# switchmod.net
KiCad netlist of a schematic drawn in EAGLE
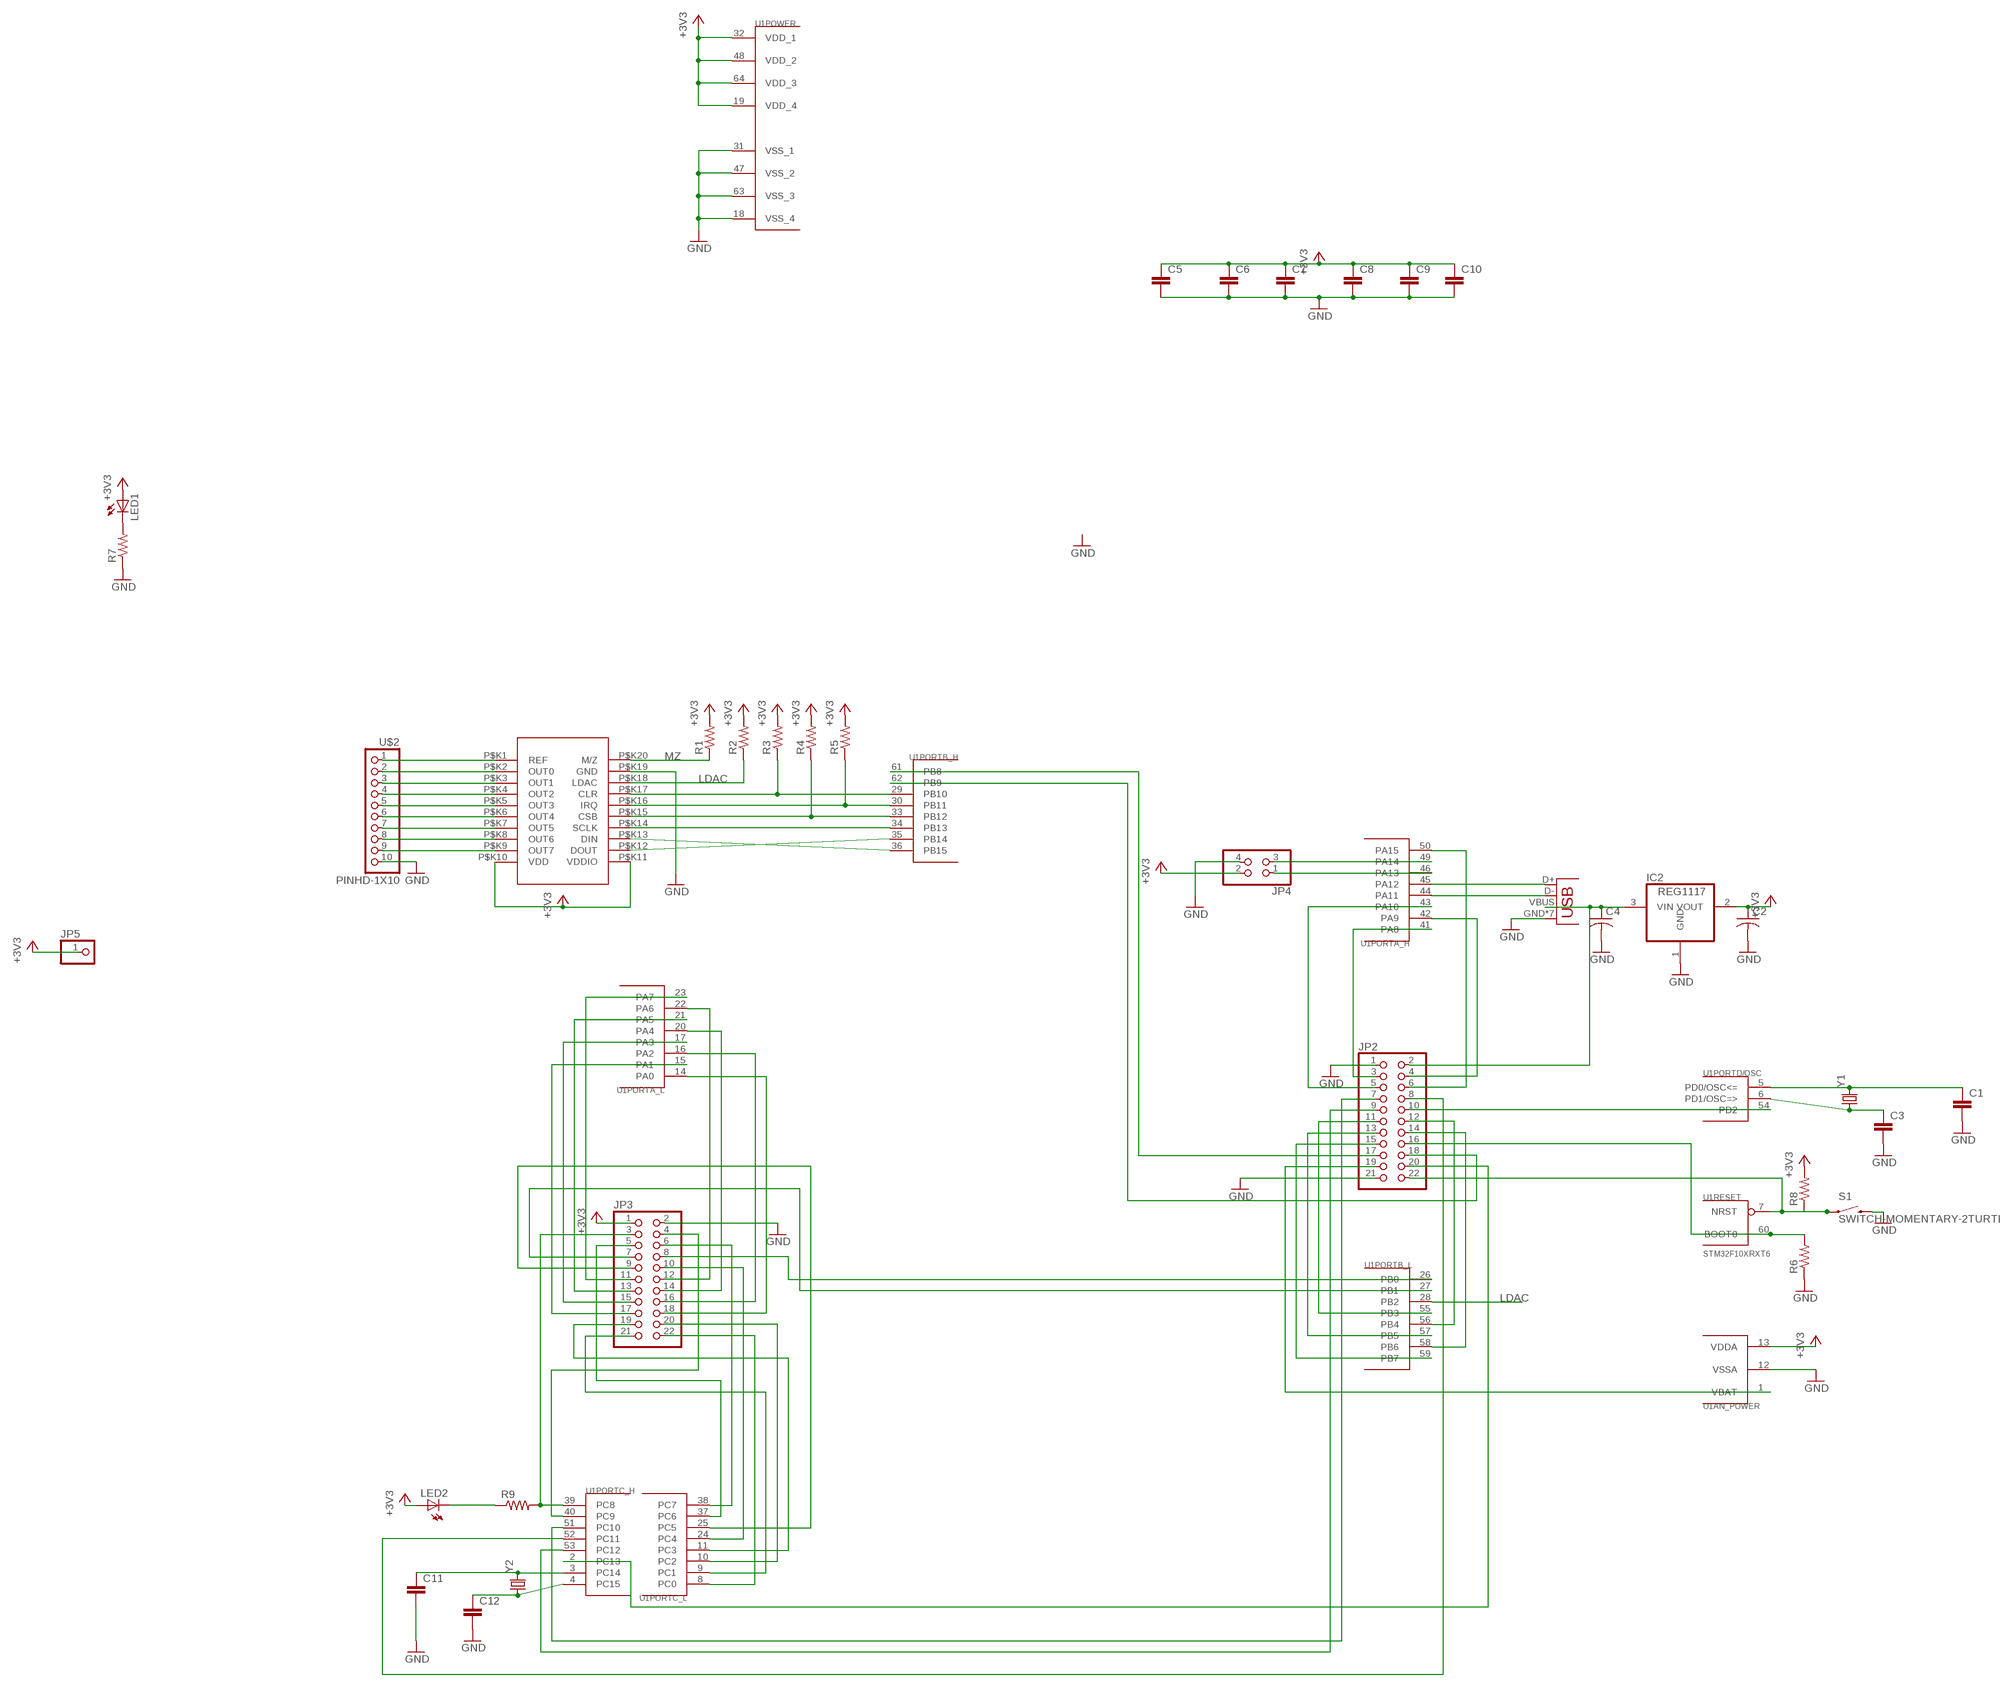
[diagram p0: schematic, sheet 1]

(export (version "E")
  (design (tool "Eeschema 10.0.6"))
  (components
    (comp (ref "C1")
      (value "CAP0805")
      (footprint "eagle-import:0805")
      (libsource (lib "eagle-import") (part "CAP0805"))
    )
    (comp (ref "C2")
      (value "C-USC1210")
      (footprint "eagle-import:C1210")
      (libsource (lib "eagle-import") (part "C-USC1210"))
    )
    (comp (ref "C3")
      (value "CAP0805")
      (footprint "eagle-import:0805")
      (libsource (lib "eagle-import") (part "CAP0805"))
    )
    (comp (ref "C4")
      (value "C-USC1210")
      (footprint "eagle-import:C1210")
      (libsource (lib "eagle-import") (part "C-USC1210"))
    )
    (comp (ref "C5")
      (value "CAP0805")
      (footprint "eagle-import:0805")
      (libsource (lib "eagle-import") (part "CAP0805"))
    )
    (comp (ref "C6")
      (value "CAP0805")
      (footprint "eagle-import:0805")
      (libsource (lib "eagle-import") (part "CAP0805"))
    )
    (comp (ref "C7")
      (value "CAP0805")
      (footprint "eagle-import:0805")
      (libsource (lib "eagle-import") (part "CAP0805"))
    )
    (comp (ref "C8")
      (value "CAP0805")
      (footprint "eagle-import:0805")
      (libsource (lib "eagle-import") (part "CAP0805"))
    )
    (comp (ref "C9")
      (value "CAP0805")
      (footprint "eagle-import:0805")
      (libsource (lib "eagle-import") (part "CAP0805"))
    )
    (comp (ref "C10")
      (value "CAP0805")
      (footprint "eagle-import:0805")
      (libsource (lib "eagle-import") (part "CAP0805"))
    )
    (comp (ref "C11")
      (value "CAP0805")
      (footprint "eagle-import:0805")
      (libsource (lib "eagle-import") (part "CAP0805"))
    )
    (comp (ref "C12")
      (value "CAP0805")
      (footprint "eagle-import:0805")
      (libsource (lib "eagle-import") (part "CAP0805"))
    )
    (comp (ref "IC2")
      (value "REG1117")
      (footprint "eagle-import:SOT223")
      (libsource (lib "eagle-import") (part "REG1117"))
    )
    (comp (ref "JP2")
      (value "PINHD-2X11")
      (footprint "eagle-import:2X11")
      (libsource (lib "eagle-import") (part "PINHD-2X11"))
    )
    (comp (ref "JP3")
      (value "PINHD-2X11")
      (footprint "eagle-import:2X11")
      (libsource (lib "eagle-import") (part "PINHD-2X11"))
    )
    (comp (ref "JP4")
      (value "PINHD-2X2")
      (footprint "eagle-import:2X02")
      (libsource (lib "eagle-import") (part "PINHD-2X2"))
    )
    (comp (ref "JP5")
      (value "PINHD-1X1")
      (footprint "eagle-import:1X01")
      (libsource (lib "eagle-import") (part "PINHD-1X1"))
    )
    (comp (ref "LED1")
      (value "LEDCHIP-LED0805")
      (footprint "eagle-import:CHIP-LED0805")
      (libsource (lib "eagle-import") (part "LEDCHIP-LED0805"))
    )
    (comp (ref "LED2")
      (value "LEDCHIP-LED0805")
      (footprint "eagle-import:CHIP-LED0805")
      (libsource (lib "eagle-import") (part "LEDCHIP-LED0805"))
    )
    (comp (ref "R1")
      (value "RESISTOR0805-RES")
      (footprint "eagle-import:0805")
      (libsource (lib "eagle-import") (part "RESISTOR0805-RES"))
    )
    (comp (ref "R2")
      (value "RESISTOR0805-RES")
      (footprint "eagle-import:0805")
      (libsource (lib "eagle-import") (part "RESISTOR0805-RES"))
    )
    (comp (ref "R3")
      (value "RESISTOR0805-RES")
      (footprint "eagle-import:0805")
      (libsource (lib "eagle-import") (part "RESISTOR0805-RES"))
    )
    (comp (ref "R4")
      (value "RESISTOR0805-RES")
      (footprint "eagle-import:0805")
      (libsource (lib "eagle-import") (part "RESISTOR0805-RES"))
    )
    (comp (ref "R5")
      (value "RESISTOR0805-RES")
      (footprint "eagle-import:0805")
      (libsource (lib "eagle-import") (part "RESISTOR0805-RES"))
    )
    (comp (ref "R6")
      (value "RESISTOR0805-RES")
      (footprint "eagle-import:0805")
      (libsource (lib "eagle-import") (part "RESISTOR0805-RES"))
    )
    (comp (ref "R7")
      (value "RESISTOR0805-RES")
      (footprint "eagle-import:0805")
      (libsource (lib "eagle-import") (part "RESISTOR0805-RES"))
    )
    (comp (ref "R8")
      (value "RESISTOR0805-RES")
      (footprint "eagle-import:0805")
      (libsource (lib "eagle-import") (part "RESISTOR0805-RES"))
    )
    (comp (ref "R9")
      (value "RESISTOR0805-RES")
      (footprint "eagle-import:0805")
      (libsource (lib "eagle-import") (part "RESISTOR0805-RES"))
    )
    (comp (ref "S1")
      (value "SWITCH-MOMENTARY-2TURTLE")
      (footprint "eagle-import:KMR2")
      (libsource (lib "eagle-import") (part "SWITCH-MOMENTARY-2TURTLE"))
    )
    (comp (ref "U$1")
      (value "MAX572X")
      (footprint "eagle-import:TSSOP20")
      (libsource (lib "eagle-import") (part "MAX572X"))
    )
    (comp (ref "U$2")
      (value "PINHD-1X10")
      (footprint "eagle-import:1X10-BIG")
      (libsource (lib "eagle-import") (part "PINHD-1X10"))
    )
    (comp (ref "U1")
      (value "STM32F10XRXT6")
      (footprint "eagle-import:TQFP64")
      (libsource (lib "eagle-import") (part "STM32F10XRXT6"))
    )
    (comp (ref "X1")
      (value "USB-MICROB")
      (footprint "eagle-import:USB-MICROB")
      (libsource (lib "eagle-import") (part "USB-MICROB"))
    )
    (comp (ref "Y1")
      (value "CRYSTALHC49US")
      (footprint "eagle-import:HC49US")
      (libsource (lib "eagle-import") (part "CRYSTALHC49US"))
    )
    (comp (ref "Y2")
      (value "CRYSTALTC26H_EZ")
      (footprint "eagle-import:TC26HEZ")
      (libsource (lib "eagle-import") (part "CRYSTALTC26H_EZ"))
    )
  )
  (nets
    (net (code "1") (name "+3V3") (class "Default")
      (node (ref "C10") (pin "1") (pinfunction "1_1") (pintype "passive"))
      (node (ref "C2") (pin "1") (pinfunction "1_1") (pintype "passive"))
      (node (ref "C5") (pin "1") (pinfunction "1_1") (pintype "passive"))
      (node (ref "C6") (pin "1") (pinfunction "1_1") (pintype "passive"))
      (node (ref "C7") (pin "1") (pinfunction "1_1") (pintype "passive"))
      (node (ref "C8") (pin "1") (pinfunction "1_1") (pintype "passive"))
      (node (ref "C9") (pin "1") (pinfunction "1_1") (pintype "passive"))
      (node (ref "IC2") (pin "2") (pinfunction "VOUT_2") (pintype "output"))
      (node (ref "JP3") (pin "1") (pinfunction "1_1") (pintype "passive"))
      (node (ref "JP4") (pin "2") (pinfunction "2_2") (pintype "passive"))
      (node (ref "JP5") (pin "1") (pinfunction "1_1") (pintype "passive"))
      (node (ref "LED1") (pin "A") (pinfunction "A_A") (pintype "passive"))
      (node (ref "LED2") (pin "A") (pinfunction "A_A") (pintype "passive"))
      (node (ref "R1") (pin "2") (pinfunction "2_2") (pintype "passive"))
      (node (ref "R2") (pin "2") (pinfunction "2_2") (pintype "passive"))
      (node (ref "R3") (pin "2") (pinfunction "2_2") (pintype "passive"))
      (node (ref "R4") (pin "2") (pinfunction "2_2") (pintype "passive"))
      (node (ref "R5") (pin "2") (pinfunction "2_2") (pintype "passive"))
      (node (ref "R8") (pin "2") (pinfunction "2_2") (pintype "passive"))
      (node (ref "U$1") (pin "P$K10") (pinfunction "VDD_P$K10") (pintype "bidirectional"))
      (node (ref "U$1") (pin "P$K11") (pinfunction "VDDIO_P$K11") (pintype "bidirectional"))
      (node (ref "U1") (pin "13") (pinfunction "VDDA_13") (pintype "power_in"))
      (node (ref "U1") (pin "19") (pinfunction "VDD_4_19") (pintype "power_in"))
      (node (ref "U1") (pin "32") (pinfunction "VDD_1_32") (pintype "power_in"))
      (node (ref "U1") (pin "48") (pinfunction "VDD_2_48") (pintype "power_in"))
      (node (ref "U1") (pin "64") (pinfunction "VDD_3_64") (pintype "power_in"))
    )
    (net (code "2") (name "/LDAC") (class "Default")
      (node (ref "R2") (pin "1") (pinfunction "1_1") (pintype "passive"))
      (node (ref "U$1") (pin "P$K18") (pinfunction "LDAC_P$K18") (pintype "bidirectional"))
      (node (ref "U1") (pin "28") (pinfunction "PB2_28") (pintype "bidirectional"))
    )
    (net (code "3") (name "/MZ") (class "Default")
      (node (ref "R1") (pin "1") (pinfunction "1_1") (pintype "passive"))
      (node (ref "U$1") (pin "P$K20") (pinfunction "M/Z_P$K20") (pintype "bidirectional"))
    )
    (net (code "4") (name "GND") (class "Default")
      (node (ref "C1") (pin "2") (pinfunction "2_2") (pintype "passive"))
      (node (ref "C10") (pin "2") (pinfunction "2_2") (pintype "passive"))
      (node (ref "C11") (pin "2") (pinfunction "2_2") (pintype "passive"))
      (node (ref "C12") (pin "2") (pinfunction "2_2") (pintype "passive"))
      (node (ref "C2") (pin "2") (pinfunction "2_2") (pintype "passive"))
      (node (ref "C3") (pin "2") (pinfunction "2_2") (pintype "passive"))
      (node (ref "C4") (pin "2") (pinfunction "2_2") (pintype "passive"))
      (node (ref "C5") (pin "2") (pinfunction "2_2") (pintype "passive"))
      (node (ref "C6") (pin "2") (pinfunction "2_2") (pintype "passive"))
      (node (ref "C7") (pin "2") (pinfunction "2_2") (pintype "passive"))
      (node (ref "C8") (pin "2") (pinfunction "2_2") (pintype "passive"))
      (node (ref "C9") (pin "2") (pinfunction "2_2") (pintype "passive"))
      (node (ref "IC2") (pin "1") (pinfunction "GND_1") (pintype "power_in"))
      (node (ref "JP2") (pin "1") (pinfunction "1_1") (pintype "passive"))
      (node (ref "JP2") (pin "21") (pinfunction "21_21") (pintype "passive"))
      (node (ref "JP3") (pin "2") (pinfunction "2_2") (pintype "passive"))
      (node (ref "JP4") (pin "4") (pinfunction "4_4") (pintype "passive"))
      (node (ref "R6") (pin "1") (pinfunction "1_1") (pintype "passive"))
      (node (ref "R7") (pin "1") (pinfunction "1_1") (pintype "passive"))
      (node (ref "S1") (pin "3") (pinfunction "2_3") (pintype "passive"))
      (node (ref "U$1") (pin "P$K19") (pinfunction "GND_P$K19") (pintype "bidirectional"))
      (node (ref "U$2") (pin "10") (pinfunction "10_10") (pintype "passive"))
      (node (ref "U1") (pin "12") (pinfunction "VSSA_12") (pintype "power_in"))
      (node (ref "U1") (pin "18") (pinfunction "VSS_4_18") (pintype "power_in"))
      (node (ref "U1") (pin "31") (pinfunction "VSS_1_31") (pintype "power_in"))
      (node (ref "U1") (pin "47") (pinfunction "VSS_2_47") (pintype "power_in"))
      (node (ref "U1") (pin "63") (pinfunction "VSS_3_63") (pintype "power_in"))
      (node (ref "X1") (pin "GND") (pinfunction "GND_GND") (pintype "bidirectional"))
      (node (ref "X1") (pin "P1") (pinfunction "GND_P1") (pintype "bidirectional"))
      (node (ref "X1") (pin "P2") (pinfunction "GND_P2") (pintype "bidirectional"))
      (node (ref "X1") (pin "P3") (pinfunction "GND_P3") (pintype "bidirectional"))
      (node (ref "X1") (pin "P4") (pinfunction "GND_P4") (pintype "bidirectional"))
      (node (ref "X1") (pin "P5") (pinfunction "GND_P5") (pintype "bidirectional"))
      (node (ref "X1") (pin "P6") (pinfunction "GND_P6") (pintype "bidirectional"))
    )
    (net (code "5") (name "Net-(IC2-VIN)") (class "Default")
      (node (ref "C4") (pin "1") (pinfunction "1_1") (pintype "passive"))
      (node (ref "IC2") (pin "3") (pinfunction "VIN_3") (pintype "input"))
      (node (ref "JP2") (pin "2") (pinfunction "2_2") (pintype "passive"))
      (node (ref "X1") (pin "VBUS") (pinfunction "VBUS_VBUS") (pintype "bidirectional"))
    )
    (net (code "6") (name "Net-(LED1-PadC)") (class "Default")
      (node (ref "LED1") (pin "C") (pinfunction "C_C") (pintype "passive"))
      (node (ref "R7") (pin "2") (pinfunction "2_2") (pintype "passive"))
    )
    (net (code "7") (name "Net-(LED2-PadC)") (class "Default")
      (node (ref "LED2") (pin "C") (pinfunction "C_C") (pintype "passive"))
      (node (ref "R9") (pin "1") (pinfunction "1_1") (pintype "passive"))
    )
    (net (code "8") (name "Net-(U$1-CLR)") (class "Default")
      (node (ref "R3") (pin "1") (pinfunction "1_1") (pintype "passive"))
      (node (ref "U$1") (pin "P$K17") (pinfunction "CLR_P$K17") (pintype "bidirectional"))
      (node (ref "U1") (pin "29") (pinfunction "PB10_29") (pintype "bidirectional"))
    )
    (net (code "9") (name "Net-(U$1-CSB)") (class "Default")
      (node (ref "R4") (pin "1") (pinfunction "1_1") (pintype "passive"))
      (node (ref "U$1") (pin "P$K15") (pinfunction "CSB_P$K15") (pintype "bidirectional"))
      (node (ref "U1") (pin "33") (pinfunction "PB12_33") (pintype "bidirectional"))
    )
    (net (code "10") (name "Net-(U$1-DIN)") (class "Default")
      (node (ref "U$1") (pin "P$K13") (pinfunction "DIN_P$K13") (pintype "bidirectional"))
      (node (ref "U1") (pin "36") (pinfunction "PB15_36") (pintype "bidirectional"))
    )
    (net (code "11") (name "Net-(U$1-DOUT)") (class "Default")
      (node (ref "U$1") (pin "P$K12") (pinfunction "DOUT_P$K12") (pintype "bidirectional"))
      (node (ref "U1") (pin "35") (pinfunction "PB14_35") (pintype "bidirectional"))
    )
    (net (code "12") (name "Net-(U$1-IRQ)") (class "Default")
      (node (ref "R5") (pin "1") (pinfunction "1_1") (pintype "passive"))
      (node (ref "U$1") (pin "P$K16") (pinfunction "IRQ_P$K16") (pintype "bidirectional"))
      (node (ref "U1") (pin "30") (pinfunction "PB11_30") (pintype "bidirectional"))
    )
    (net (code "13") (name "Net-(U$1-OUT0)") (class "Default")
      (node (ref "U$1") (pin "P$K2") (pinfunction "OUT0_P$K2") (pintype "bidirectional"))
      (node (ref "U$2") (pin "2") (pinfunction "2_2") (pintype "passive"))
    )
    (net (code "14") (name "Net-(U$1-OUT1)") (class "Default")
      (node (ref "U$1") (pin "P$K3") (pinfunction "OUT1_P$K3") (pintype "bidirectional"))
      (node (ref "U$2") (pin "3") (pinfunction "3_3") (pintype "passive"))
    )
    (net (code "15") (name "Net-(U$1-OUT2)") (class "Default")
      (node (ref "U$1") (pin "P$K4") (pinfunction "OUT2_P$K4") (pintype "bidirectional"))
      (node (ref "U$2") (pin "4") (pinfunction "4_4") (pintype "passive"))
    )
    (net (code "16") (name "Net-(U$1-OUT3)") (class "Default")
      (node (ref "U$1") (pin "P$K5") (pinfunction "OUT3_P$K5") (pintype "bidirectional"))
      (node (ref "U$2") (pin "5") (pinfunction "5_5") (pintype "passive"))
    )
    (net (code "17") (name "Net-(U$1-OUT4)") (class "Default")
      (node (ref "U$1") (pin "P$K6") (pinfunction "OUT4_P$K6") (pintype "bidirectional"))
      (node (ref "U$2") (pin "6") (pinfunction "6_6") (pintype "passive"))
    )
    (net (code "18") (name "Net-(U$1-OUT5)") (class "Default")
      (node (ref "U$1") (pin "P$K7") (pinfunction "OUT5_P$K7") (pintype "bidirectional"))
      (node (ref "U$2") (pin "7") (pinfunction "7_7") (pintype "passive"))
    )
    (net (code "19") (name "Net-(U$1-OUT6)") (class "Default")
      (node (ref "U$1") (pin "P$K8") (pinfunction "OUT6_P$K8") (pintype "bidirectional"))
      (node (ref "U$2") (pin "8") (pinfunction "8_8") (pintype "passive"))
    )
    (net (code "20") (name "Net-(U$1-OUT7)") (class "Default")
      (node (ref "U$1") (pin "P$K9") (pinfunction "OUT7_P$K9") (pintype "bidirectional"))
      (node (ref "U$2") (pin "9") (pinfunction "9_9") (pintype "passive"))
    )
    (net (code "21") (name "Net-(U$1-REF)") (class "Default")
      (node (ref "U$1") (pin "P$K1") (pinfunction "REF_P$K1") (pintype "bidirectional"))
      (node (ref "U$2") (pin "1") (pinfunction "1_1") (pintype "passive"))
    )
    (net (code "22") (name "Net-(U$1-SCLK)") (class "Default")
      (node (ref "U$1") (pin "P$K14") (pinfunction "SCLK_P$K14") (pintype "bidirectional"))
      (node (ref "U1") (pin "34") (pinfunction "PB13_34") (pintype "bidirectional"))
    )
    (net (code "23") (name "Net-(U1A-VBAT)") (class "Default")
      (node (ref "JP2") (pin "19") (pinfunction "19_19") (pintype "passive"))
      (node (ref "U1") (pin "1") (pinfunction "VBAT_1") (pintype "power_in"))
    )
    (net (code "24") (name "Net-(U1B-PA8)") (class "Default")
      (node (ref "JP2") (pin "3") (pinfunction "3_3") (pintype "passive"))
      (node (ref "U1") (pin "41") (pinfunction "PA8_41") (pintype "bidirectional"))
    )
    (net (code "25") (name "Net-(U1B-PA9)") (class "Default")
      (node (ref "JP2") (pin "4") (pinfunction "4_4") (pintype "passive"))
      (node (ref "U1") (pin "42") (pinfunction "PA9_42") (pintype "bidirectional"))
    )
    (net (code "26") (name "Net-(U1B-PA10)") (class "Default")
      (node (ref "JP2") (pin "5") (pinfunction "5_5") (pintype "passive"))
      (node (ref "U1") (pin "43") (pinfunction "PA10_43") (pintype "bidirectional"))
    )
    (net (code "27") (name "Net-(U1B-PA11)") (class "Default")
      (node (ref "U1") (pin "44") (pinfunction "PA11_44") (pintype "bidirectional"))
      (node (ref "X1") (pin "D-") (pinfunction "D-_D-") (pintype "bidirectional"))
    )
    (net (code "28") (name "Net-(U1B-PA12)") (class "Default")
      (node (ref "U1") (pin "45") (pinfunction "PA12_45") (pintype "bidirectional"))
      (node (ref "X1") (pin "D+") (pinfunction "D+_D+") (pintype "bidirectional"))
    )
    (net (code "29") (name "Net-(U1B-PA13)") (class "Default")
      (node (ref "JP4") (pin "1") (pinfunction "1_1") (pintype "passive"))
      (node (ref "U1") (pin "46") (pinfunction "PA13_46") (pintype "bidirectional"))
    )
    (net (code "30") (name "Net-(U1B-PA14)") (class "Default")
      (node (ref "JP4") (pin "3") (pinfunction "3_3") (pintype "passive"))
      (node (ref "U1") (pin "49") (pinfunction "PA14_49") (pintype "bidirectional"))
    )
    (net (code "31") (name "Net-(U1B-PA15)") (class "Default")
      (node (ref "JP2") (pin "6") (pinfunction "6_6") (pintype "passive"))
      (node (ref "U1") (pin "50") (pinfunction "PA15_50") (pintype "bidirectional"))
    )
    (net (code "32") (name "Net-(U1C-PA0)") (class "Default")
      (node (ref "JP3") (pin "18") (pinfunction "18_18") (pintype "passive"))
      (node (ref "U1") (pin "14") (pinfunction "PA0_14") (pintype "bidirectional"))
    )
    (net (code "33") (name "Net-(U1C-PA1)") (class "Default")
      (node (ref "JP3") (pin "17") (pinfunction "17_17") (pintype "passive"))
      (node (ref "U1") (pin "15") (pinfunction "PA1_15") (pintype "bidirectional"))
    )
    (net (code "34") (name "Net-(U1C-PA2)") (class "Default")
      (node (ref "JP3") (pin "16") (pinfunction "16_16") (pintype "passive"))
      (node (ref "U1") (pin "16") (pinfunction "PA2_16") (pintype "bidirectional"))
    )
    (net (code "35") (name "Net-(U1C-PA3)") (class "Default")
      (node (ref "JP3") (pin "15") (pinfunction "15_15") (pintype "passive"))
      (node (ref "U1") (pin "17") (pinfunction "PA3_17") (pintype "bidirectional"))
    )
    (net (code "36") (name "Net-(U1C-PA4)") (class "Default")
      (node (ref "JP3") (pin "14") (pinfunction "14_14") (pintype "passive"))
      (node (ref "U1") (pin "20") (pinfunction "PA4_20") (pintype "bidirectional"))
    )
    (net (code "37") (name "Net-(U1C-PA5)") (class "Default")
      (node (ref "JP3") (pin "13") (pinfunction "13_13") (pintype "passive"))
      (node (ref "U1") (pin "21") (pinfunction "PA5_21") (pintype "bidirectional"))
    )
    (net (code "38") (name "Net-(U1C-PA6)") (class "Default")
      (node (ref "JP3") (pin "12") (pinfunction "12_12") (pintype "passive"))
      (node (ref "U1") (pin "22") (pinfunction "PA6_22") (pintype "bidirectional"))
    )
    (net (code "39") (name "Net-(U1C-PA7)") (class "Default")
      (node (ref "JP3") (pin "11") (pinfunction "11_11") (pintype "passive"))
      (node (ref "U1") (pin "23") (pinfunction "PA7_23") (pintype "bidirectional"))
    )
    (net (code "40") (name "Net-(U1D-PB8)") (class "Default")
      (node (ref "JP2") (pin "17") (pinfunction "17_17") (pintype "passive"))
      (node (ref "U1") (pin "61") (pinfunction "PB8_61") (pintype "bidirectional"))
    )
    (net (code "41") (name "Net-(U1D-PB9)") (class "Default")
      (node (ref "JP2") (pin "18") (pinfunction "18_18") (pintype "passive"))
      (node (ref "U1") (pin "62") (pinfunction "PB9_62") (pintype "bidirectional"))
    )
    (net (code "42") (name "Net-(U1E-PB0)") (class "Default")
      (node (ref "JP3") (pin "8") (pinfunction "8_8") (pintype "passive"))
      (node (ref "U1") (pin "26") (pinfunction "PB0_26") (pintype "bidirectional"))
    )
    (net (code "43") (name "Net-(U1E-PB1)") (class "Default")
      (node (ref "JP3") (pin "7") (pinfunction "7_7") (pintype "passive"))
      (node (ref "U1") (pin "27") (pinfunction "PB1_27") (pintype "bidirectional"))
    )
    (net (code "44") (name "Net-(U1E-PB3)") (class "Default")
      (node (ref "JP2") (pin "11") (pinfunction "11_11") (pintype "passive"))
      (node (ref "U1") (pin "55") (pinfunction "PB3_55") (pintype "bidirectional"))
    )
    (net (code "45") (name "Net-(U1E-PB4)") (class "Default")
      (node (ref "JP2") (pin "12") (pinfunction "12_12") (pintype "passive"))
      (node (ref "U1") (pin "56") (pinfunction "PB4_56") (pintype "bidirectional"))
    )
    (net (code "46") (name "Net-(U1E-PB5)") (class "Default")
      (node (ref "JP2") (pin "13") (pinfunction "13_13") (pintype "passive"))
      (node (ref "U1") (pin "57") (pinfunction "PB5_57") (pintype "bidirectional"))
    )
    (net (code "47") (name "Net-(U1E-PB6)") (class "Default")
      (node (ref "JP2") (pin "14") (pinfunction "14_14") (pintype "passive"))
      (node (ref "U1") (pin "58") (pinfunction "PB6_58") (pintype "bidirectional"))
    )
    (net (code "48") (name "Net-(U1E-PB7)") (class "Default")
      (node (ref "JP2") (pin "15") (pinfunction "15_15") (pintype "passive"))
      (node (ref "U1") (pin "59") (pinfunction "PB7_59") (pintype "bidirectional"))
    )
    (net (code "49") (name "Net-(U1F-PC8)") (class "Default")
      (node (ref "JP3") (pin "3") (pinfunction "3_3") (pintype "passive"))
      (node (ref "R9") (pin "2") (pinfunction "2_2") (pintype "passive"))
      (node (ref "U1") (pin "39") (pinfunction "PC8_39") (pintype "bidirectional"))
    )
    (net (code "50") (name "Net-(U1F-PC9)") (class "Default")
      (node (ref "JP3") (pin "4") (pinfunction "4_4") (pintype "passive"))
      (node (ref "U1") (pin "40") (pinfunction "PC9_40") (pintype "bidirectional"))
    )
    (net (code "51") (name "Net-(U1F-PC10)") (class "Default")
      (node (ref "JP2") (pin "7") (pinfunction "7_7") (pintype "passive"))
      (node (ref "U1") (pin "51") (pinfunction "PC10_51") (pintype "bidirectional"))
    )
    (net (code "52") (name "Net-(U1F-PC11)") (class "Default")
      (node (ref "JP2") (pin "8") (pinfunction "8_8") (pintype "passive"))
      (node (ref "U1") (pin "52") (pinfunction "PC11_52") (pintype "bidirectional"))
    )
    (net (code "53") (name "Net-(U1F-PC12)") (class "Default")
      (node (ref "JP2") (pin "9") (pinfunction "9_9") (pintype "passive"))
      (node (ref "U1") (pin "53") (pinfunction "PC12_53") (pintype "bidirectional"))
    )
    (net (code "54") (name "Net-(U1F-PC13)") (class "Default")
      (node (ref "JP2") (pin "20") (pinfunction "20_20") (pintype "passive"))
      (node (ref "U1") (pin "2") (pinfunction "PC13_2") (pintype "bidirectional"))
    )
    (net (code "55") (name "Net-(U1F-PC14)") (class "Default")
      (node (ref "C11") (pin "1") (pinfunction "1_1") (pintype "passive"))
      (node (ref "U1") (pin "3") (pinfunction "PC14_3") (pintype "bidirectional"))
      (node (ref "Y2") (pin "2") (pinfunction "2_2") (pintype "passive"))
    )
    (net (code "56") (name "Net-(U1F-PC15)") (class "Default")
      (node (ref "C12") (pin "1") (pinfunction "1_1") (pintype "passive"))
      (node (ref "U1") (pin "4") (pinfunction "PC15_4") (pintype "bidirectional"))
      (node (ref "Y2") (pin "1") (pinfunction "1_1") (pintype "passive"))
    )
    (net (code "57") (name "Net-(U1G-PC0)") (class "Default")
      (node (ref "JP3") (pin "22") (pinfunction "22_22") (pintype "passive"))
      (node (ref "U1") (pin "8") (pinfunction "PC0_8") (pintype "bidirectional"))
    )
    (net (code "58") (name "Net-(U1G-PC1)") (class "Default")
      (node (ref "JP3") (pin "21") (pinfunction "21_21") (pintype "passive"))
      (node (ref "U1") (pin "9") (pinfunction "PC1_9") (pintype "bidirectional"))
    )
    (net (code "59") (name "Net-(U1G-PC2)") (class "Default")
      (node (ref "JP3") (pin "20") (pinfunction "20_20") (pintype "passive"))
      (node (ref "U1") (pin "10") (pinfunction "PC2_10") (pintype "bidirectional"))
    )
    (net (code "60") (name "Net-(U1G-PC3)") (class "Default")
      (node (ref "JP3") (pin "19") (pinfunction "19_19") (pintype "passive"))
      (node (ref "U1") (pin "11") (pinfunction "PC3_11") (pintype "bidirectional"))
    )
    (net (code "61") (name "Net-(U1G-PC4)") (class "Default")
      (node (ref "JP3") (pin "10") (pinfunction "10_10") (pintype "passive"))
      (node (ref "U1") (pin "24") (pinfunction "PC4_24") (pintype "bidirectional"))
    )
    (net (code "62") (name "Net-(U1G-PC5)") (class "Default")
      (node (ref "JP3") (pin "9") (pinfunction "9_9") (pintype "passive"))
      (node (ref "U1") (pin "25") (pinfunction "PC5_25") (pintype "bidirectional"))
    )
    (net (code "63") (name "Net-(U1G-PC6)") (class "Default")
      (node (ref "JP3") (pin "5") (pinfunction "5_5") (pintype "passive"))
      (node (ref "U1") (pin "37") (pinfunction "PC6_37") (pintype "bidirectional"))
    )
    (net (code "64") (name "Net-(U1G-PC7)") (class "Default")
      (node (ref "JP3") (pin "6") (pinfunction "6_6") (pintype "passive"))
      (node (ref "U1") (pin "38") (pinfunction "PC7_38") (pintype "bidirectional"))
    )
    (net (code "65") (name "Net-(U1H-PD0{slash}OSC<=)") (class "Default")
      (node (ref "C1") (pin "1") (pinfunction "1_1") (pintype "passive"))
      (node (ref "U1") (pin "5") (pinfunction "PD0/OSC<=_5") (pintype "bidirectional"))
      (node (ref "Y1") (pin "2") (pinfunction "2_2") (pintype "passive"))
    )
    (net (code "66") (name "Net-(U1H-PD1{slash}OSC=>)") (class "Default")
      (node (ref "C3") (pin "1") (pinfunction "1_1") (pintype "passive"))
      (node (ref "U1") (pin "6") (pinfunction "PD1/OSC=>_6") (pintype "bidirectional"))
      (node (ref "Y1") (pin "1") (pinfunction "1_1") (pintype "passive"))
    )
    (net (code "67") (name "Net-(U1H-PD2)") (class "Default")
      (node (ref "JP2") (pin "10") (pinfunction "10_10") (pintype "passive"))
      (node (ref "U1") (pin "54") (pinfunction "PD2_54") (pintype "bidirectional"))
    )
    (net (code "68") (name "Net-(U1J-BOOT0)") (class "Default")
      (node (ref "JP2") (pin "16") (pinfunction "16_16") (pintype "passive"))
      (node (ref "R6") (pin "2") (pinfunction "2_2") (pintype "passive"))
      (node (ref "U1") (pin "60") (pinfunction "BOOT0_60") (pintype "input"))
    )
    (net (code "69") (name "Net-(U1J-NRST)") (class "Default")
      (node (ref "JP2") (pin "22") (pinfunction "22_22") (pintype "passive"))
      (node (ref "R8") (pin "1") (pinfunction "1_1") (pintype "passive"))
      (node (ref "S1") (pin "1") (pinfunction "1_1") (pintype "passive"))
      (node (ref "U1") (pin "7") (pinfunction "NRST_7") (pintype "input"))
    )
  )
)
